# page1.net
KiCad netlist of a schematic drawn in Altium Designer
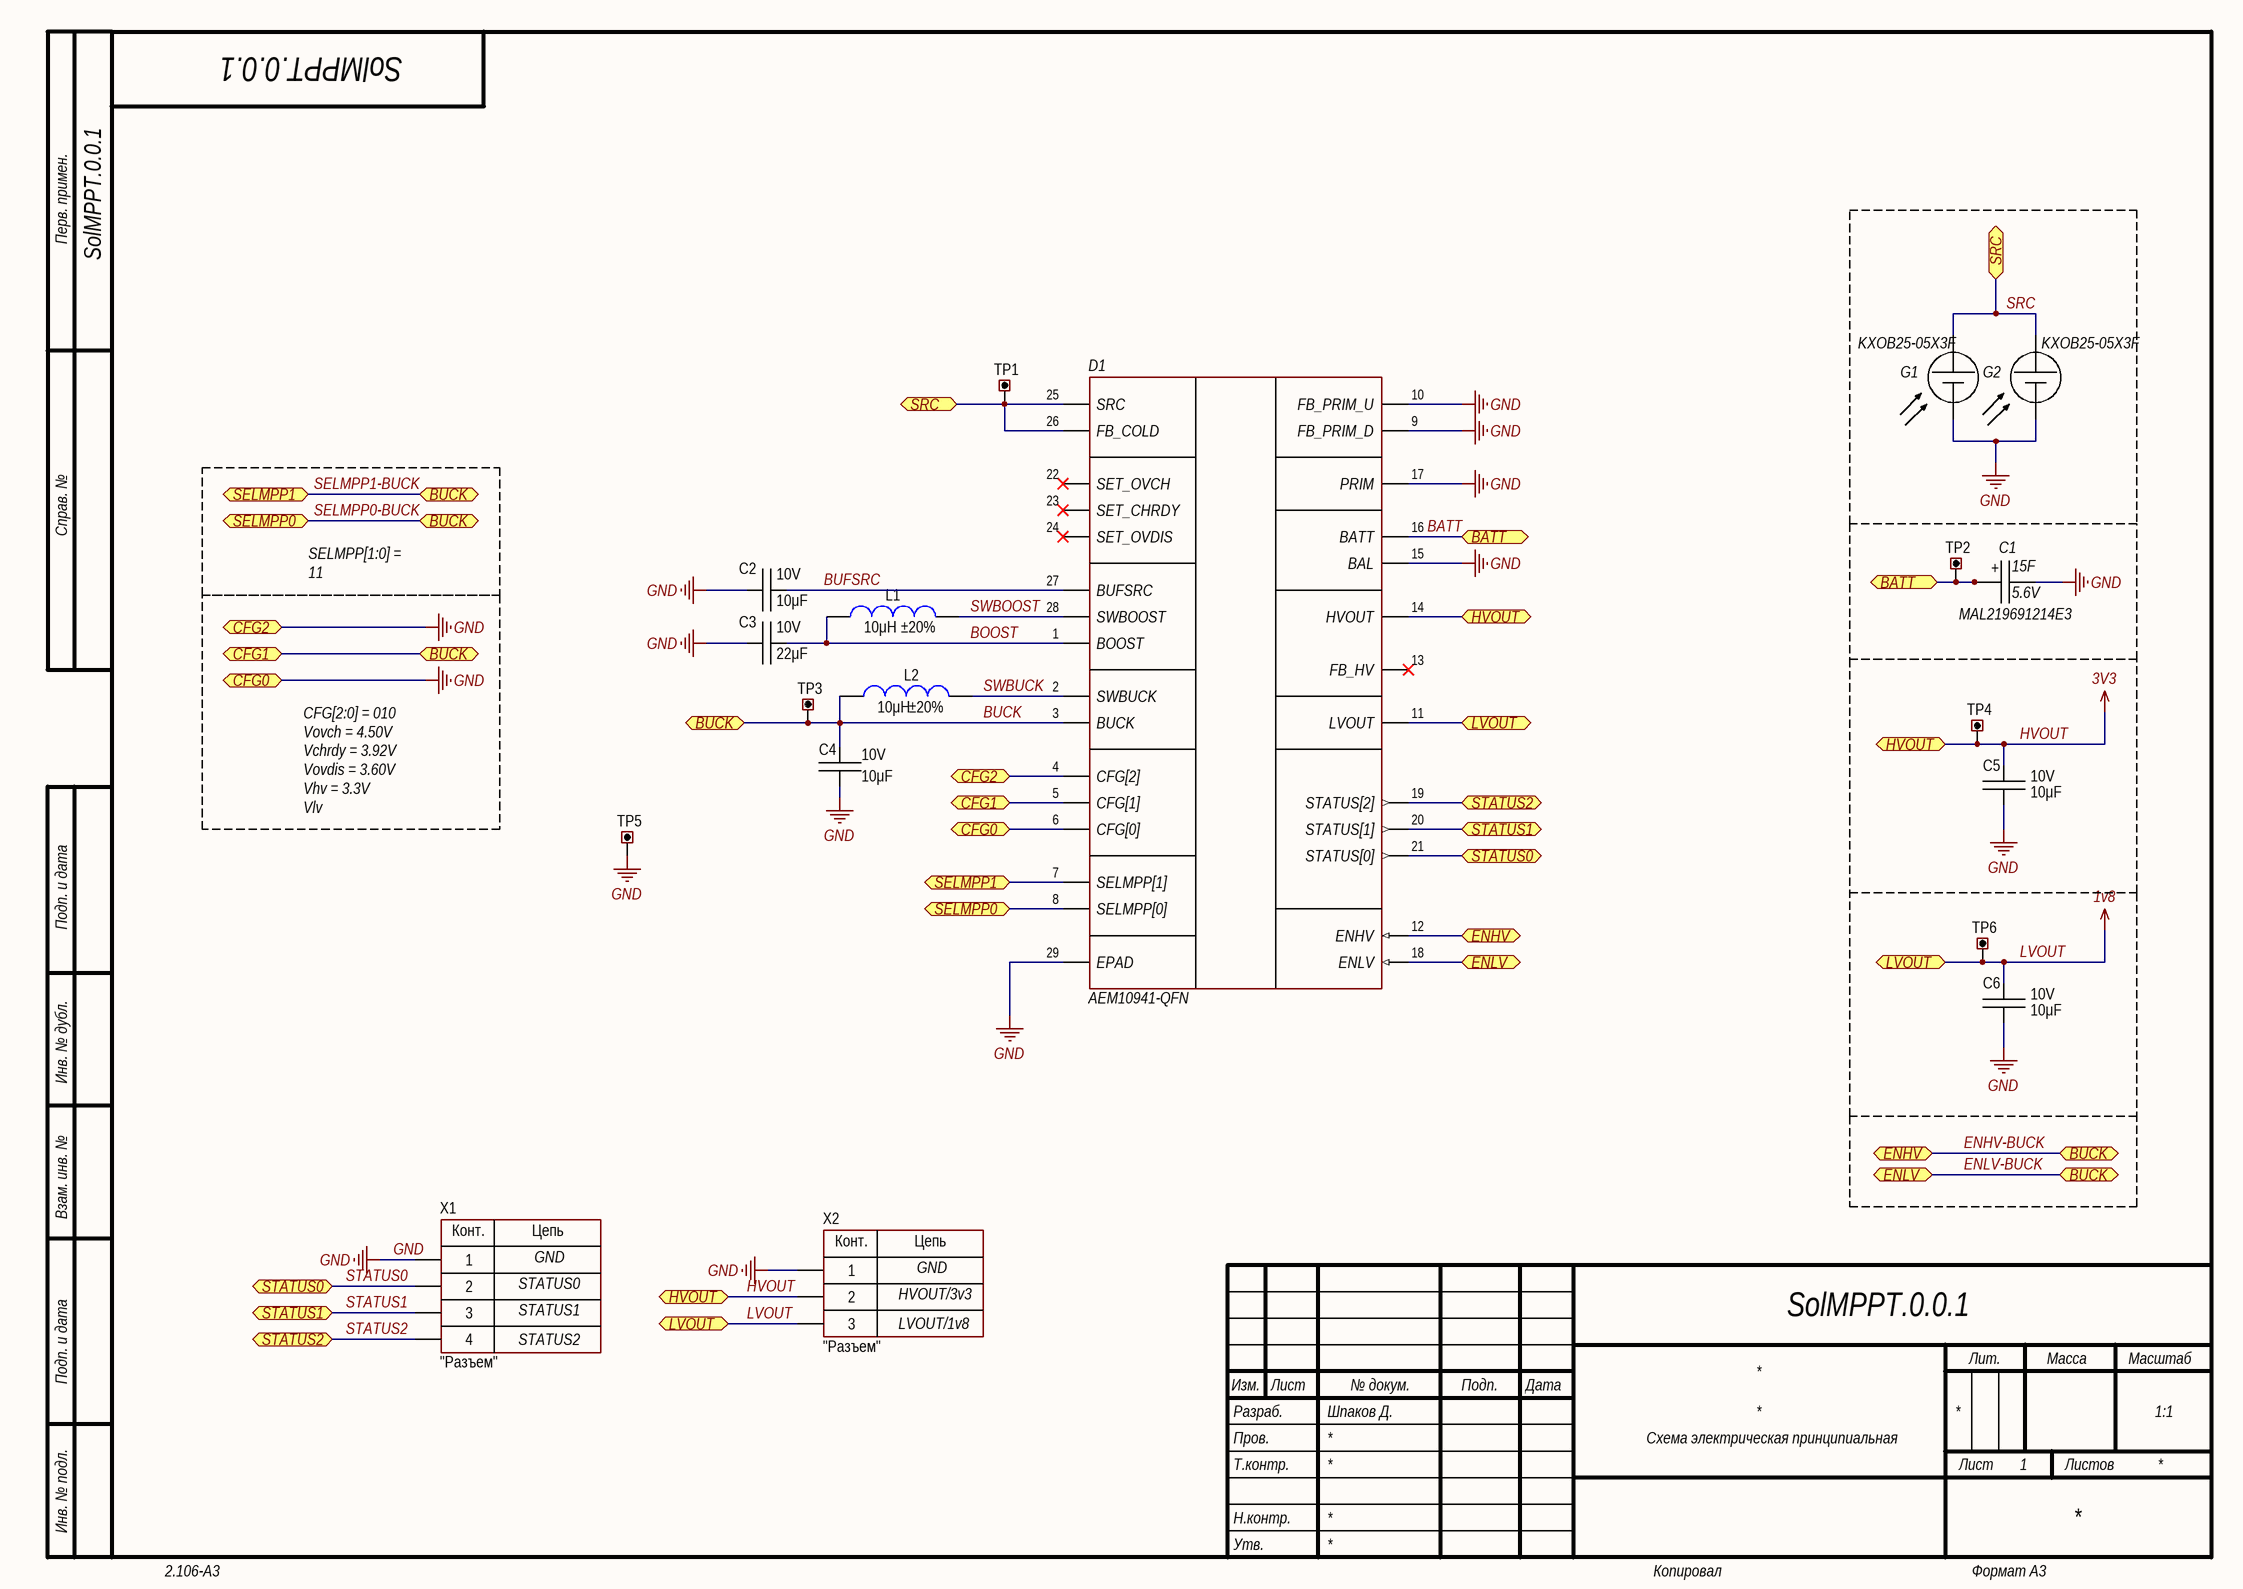
[diagram p0: page1.SchDoc]

(export (version "E")
  (design (tool "Eeschema 10.0.6"))
  (components
    (comp (ref "C1")
      (value "15F")
      (footprint "MAL219691214E3")
      (description "CAP 15F -20% +80% 5.6V T/H")
      (fields
        (field (name "MANUFACTURER") "Vishay Beyschlag/Draloric/BC Components")
        (field (name "PARTNUMBER") "MAL219691214E3")
        (field (name "VOLTAGE") "5.6V")
      )
      (libsource (lib "MAL219691214E3") (part "MAL219691214E3"))
    )
    (comp (ref "C2")
      (value "10μF")
      (footprint "CAP: 0603")
      (fields
        (field (name "MANUFACTURER") "Murata Electronics")
        (field (name "PARTNUMBER") "GRM188R61A106ME69D")
        (field (name "VALUEMANUFACTURERPARTNUMBER") "Ceramic capacitor, 10μF, X5R, ±20%, 10V, 0603, -55...+85°C")
        (field (name "VOLTAGE") "10V")
      )
      (libsource (lib "capacitor") (part "Ceramic_0603"))
    )
    (comp (ref "C3")
      (value "22μF")
      (footprint "CAP: 0603")
      (fields
        (field (name "MANUFACTURER") "Murata Electronics")
        (field (name "PARTNUMBER") "GRM188R61A226ME15D")
        (field (name "VALUEMANUFACTURERPARTNUMBER") "Ceramic capacitor, 22μF, X5R, ±20%, 10V, 0603, -55...+85°C")
        (field (name "VOLTAGE") "10V")
      )
      (libsource (lib "capacitor") (part "Ceramic_0603"))
    )
    (comp (ref "C4")
      (value "10μF")
      (footprint "CAP: 0603")
      (fields
        (field (name "MANUFACTURER") "Murata Electronics")
        (field (name "PARTNUMBER") "GRM188R61A106ME69D")
        (field (name "VALUEMANUFACTURERPARTNUMBER") "Ceramic capacitor, 10μF, X5R, ±20%, 10V, 0603, -55...+85°C")
        (field (name "VOLTAGE") "10V")
      )
      (libsource (lib "capacitor") (part "Ceramic_0603"))
    )
    (comp (ref "C5")
      (value "10μF")
      (footprint "CAP: 0603")
      (fields
        (field (name "MANUFACTURER") "Murata Electronics")
        (field (name "PARTNUMBER") "GRM188R61A106ME69D")
        (field (name "VALUEMANUFACTURERPARTNUMBER") "Ceramic capacitor, 10μF, X5R, ±20%, 10V, 0603, -55...+85°C")
        (field (name "VOLTAGE") "10V")
      )
      (libsource (lib "capacitor") (part "Ceramic_0603"))
    )
    (comp (ref "C6")
      (value "10μF")
      (footprint "CAP: 0603")
      (fields
        (field (name "MANUFACTURER") "Murata Electronics")
        (field (name "PARTNUMBER") "GRM188R61A106ME69D")
        (field (name "VALUEMANUFACTURERPARTNUMBER") "Ceramic capacitor, 10μF, X5R, ±20%, 10V, 0603, -55...+85°C")
        (field (name "VOLTAGE") "10V")
      )
      (libsource (lib "capacitor") (part "Ceramic_0603"))
    )
    (comp (ref "D1")
      (value "AEM10941-QFN")
      (footprint "QFN50P500X500X85_HS-29N")
      (description "Power Management Specialised - PMIC AEM10941 IC - Photovoltaic Energy Harvesting Manager.")
      (fields (field (name "MANUFACTURER") "e-peas"))
      (libsource (lib "AEM10941") (part "AEM10941"))
    )
    (comp (ref "G1")
      (value "KXOB25-05X3F")
      (footprint "KXOB25-05X3F")
      (description "Monocrystalline solar cell.")
      (fields (field (name "MANUFACTURER") "ANYSOLAR Ltd"))
      (libsource (lib "Solar_cell") (part "KXOB25-05X3F"))
    )
    (comp (ref "G2")
      (value "KXOB25-05X3F")
      (footprint "KXOB25-05X3F")
      (description "Monocrystalline solar cell.")
      (fields (field (name "MANUFACTURER") "ANYSOLAR Ltd"))
      (libsource (lib "Solar_cell") (part "KXOB25-05X3F"))
    )
    (comp (ref "L1")
      (value "10μH")
      (footprint "IND: SDR0302")
      (fields
        (field (name "MANUFACTURER") "Bourns")
        (field (name "PARTNUMBER") "SDR0302-100ML")
        (field (name "VALUEMANUFACTURERPARTNUMBER") "Fixed inductor, 10μH, ±20%, SDR0302, 900mA, -40...+125°C")
        (field (name "TOLERANCE") "±20%")
      )
      (libsource (lib "inductor") (part "Inductor_SDR0302"))
    )
    (comp (ref "L2")
      (value "10μH")
      (footprint "IND: 0603")
      (fields
        (field (name "MANUFACTURER") "TDK Corporation")
        (field (name "PARTNUMBER") "MLZ1608M100WT000")
        (field (name "VALUEMANUFACTURERPARTNUMBER") "Fixed inductor, 10μH, ±20%, 0603, 250mA, -55...+125°C")
        (field (name "TOLERANCE") "±20%")
      )
      (libsource (lib "inductor") (part "Inductor_0603"))
    )
    (comp (ref "TP1")
      (value "~")
      (footprint "CON: 5000 (Keystone)")
      (fields
        (field (name "MANUFACTURER") "Keystone")
        (field (name "VALUEMANUFACTURERPARTNUMBER") "Test point, Keystone, 5001")
        (field (name "PARTNUMBER") "5001")
      )
      (libsource (lib "connector") (part "Connector_Test_Point"))
    )
    (comp (ref "TP2")
      (value "~")
      (footprint "CON: 5000 (Keystone)")
      (fields
        (field (name "MANUFACTURER") "Keystone")
        (field (name "VALUEMANUFACTURERPARTNUMBER") "Test point, Keystone, 5001")
        (field (name "PARTNUMBER") "5001")
      )
      (libsource (lib "connector") (part "Connector_Test_Point"))
    )
    (comp (ref "TP3")
      (value "~")
      (footprint "CON: 5000 (Keystone)")
      (fields
        (field (name "MANUFACTURER") "Keystone")
        (field (name "VALUEMANUFACTURERPARTNUMBER") "Test point, Keystone, 5001")
        (field (name "PARTNUMBER") "5001")
      )
      (libsource (lib "connector") (part "Connector_Test_Point"))
    )
    (comp (ref "TP4")
      (value "~")
      (footprint "CON: 5000 (Keystone)")
      (fields
        (field (name "MANUFACTURER") "Keystone")
        (field (name "VALUEMANUFACTURERPARTNUMBER") "Test point, Keystone, 5001")
        (field (name "PARTNUMBER") "5001")
      )
      (libsource (lib "connector") (part "Connector_Test_Point"))
    )
    (comp (ref "TP5")
      (value "~")
      (footprint "CON: 5000 (Keystone)")
      (fields
        (field (name "MANUFACTURER") "Keystone")
        (field (name "VALUEMANUFACTURERPARTNUMBER") "Test point, Keystone, 5001")
        (field (name "PARTNUMBER") "5001")
      )
      (libsource (lib "connector") (part "Connector_Test_Point"))
    )
    (comp (ref "TP6")
      (value "~")
      (footprint "CON: 5000 (Keystone)")
      (fields
        (field (name "MANUFACTURER") "Keystone")
        (field (name "VALUEMANUFACTURERPARTNUMBER") "Test point, Keystone, 5001")
        (field (name "PARTNUMBER") "5001")
      )
      (libsource (lib "connector") (part "Connector_Test_Point"))
    )
    (comp (ref "X1")
      (value "~")
      (footprint "CON: PLS-4")
      (fields
        (field (name "MANUFACTURER") "Connfly")
        (field (name "VALUEMANUFACTURERPARTNUMBER") "Connector, 4pin, 2.54mm, 500VAC, 3A")
        (field (name "PARTNUMBER") "PLS-4")
        (field (name "COMMENTTEXT") "\"Разъем\"")
      )
      (libsource (lib "connector") (part "PLS-4"))
    )
    (comp (ref "X2")
      (value "~")
      (footprint "CON: PLS-3")
      (fields
        (field (name "MANUFACTURER") "Connfly")
        (field (name "VALUEMANUFACTURERPARTNUMBER") "Connector, 3pin, 2.54mm, 500VAC, 3A")
        (field (name "PARTNUMBER") "PLS-3")
        (field (name "COMMENTTEXT") "\"Разъем\"")
      )
      (libsource (lib "connector") (part "PLS-3"))
    )
  )
  (nets
    (net (code "1") (name "/BATT") (class "Default")
      (node (ref "C1") (pin "1") (pintype "power_in"))
      (node (ref "C1") (pin "1a") (pintype "power_in"))
      (node (ref "D1") (pin "16") (pinfunction "BATT_16") (pintype "power_in"))
      (node (ref "TP2") (pin "1") (pinfunction "1_1") (pintype "passive"))
    )
    (net (code "2") (name "/BOOST") (class "Default")
      (node (ref "C3") (pin "1") (pinfunction "1_1") (pintype "passive"))
      (node (ref "D1") (pin "1") (pinfunction "BOOST_1") (pintype "power_in"))
      (node (ref "L1") (pin "2") (pinfunction "2_2") (pintype "passive"))
    )
    (net (code "3") (name "/BUCK") (class "Default")
      (node (ref "C4") (pin "1") (pinfunction "1_1") (pintype "passive"))
      (node (ref "D1") (pin "12") (pinfunction "ENHV_12") (pintype "input"))
      (node (ref "D1") (pin "18") (pinfunction "ENLV_18") (pintype "input"))
      (node (ref "D1") (pin "3") (pinfunction "BUCK_3") (pintype "power_in"))
      (node (ref "D1") (pin "5") (pinfunction "CFG[1]_5") (pintype "power_in"))
      (node (ref "D1") (pin "7") (pinfunction "SELMPP[1]_7") (pintype "power_in"))
      (node (ref "D1") (pin "8") (pinfunction "SELMPP[0]_8") (pintype "power_in"))
      (node (ref "L2") (pin "2") (pinfunction "2_2") (pintype "passive"))
      (node (ref "TP3") (pin "1") (pinfunction "1_1") (pintype "passive"))
    )
    (net (code "4") (name "/BUFSRC") (class "Default")
      (node (ref "C2") (pin "2") (pinfunction "2_2") (pintype "passive"))
      (node (ref "D1") (pin "27") (pinfunction "BUFSRC_27") (pintype "power_in"))
    )
    (net (code "5") (name "/SRC") (class "Default")
      (node (ref "D1") (pin "25") (pinfunction "SRC_25") (pintype "power_in"))
      (node (ref "D1") (pin "26") (pinfunction "FB_COLD_26") (pintype "power_in"))
      (node (ref "G1") (pin "1") (pintype "power_in"))
      (node (ref "G2") (pin "1") (pintype "power_in"))
      (node (ref "TP1") (pin "1") (pinfunction "1_1") (pintype "passive"))
    )
    (net (code "6") (name "/STATUS0") (class "Default")
      (node (ref "D1") (pin "21") (pinfunction "STATUS[0]_21") (pintype "output"))
      (node (ref "X1") (pin "2") (pinfunction "2_2") (pintype "passive"))
    )
    (net (code "7") (name "/STATUS1") (class "Default")
      (node (ref "D1") (pin "20") (pinfunction "STATUS[1]_20") (pintype "output"))
      (node (ref "X1") (pin "3") (pinfunction "3_3") (pintype "power_in"))
    )
    (net (code "8") (name "/STATUS2") (class "Default")
      (node (ref "D1") (pin "19") (pinfunction "STATUS[2]_19") (pintype "output"))
      (node (ref "X1") (pin "4") (pinfunction "4_4") (pintype "power_in"))
    )
    (net (code "9") (name "/SWBOOST") (class "Default")
      (node (ref "D1") (pin "28") (pinfunction "SWBOOST_28") (pintype "power_in"))
      (node (ref "L1") (pin "1") (pinfunction "1_1") (pintype "passive"))
    )
    (net (code "10") (name "/SWBUCK") (class "Default")
      (node (ref "D1") (pin "2") (pinfunction "SWBUCK_2") (pintype "power_in"))
      (node (ref "L2") (pin "1") (pinfunction "1_1") (pintype "passive"))
    )
    (net (code "11") (name "1v8") (class "Default")
      (node (ref "C6") (pin "1") (pinfunction "1_1") (pintype "passive"))
      (node (ref "D1") (pin "11") (pinfunction "LVOUT_11") (pintype "power_in"))
      (node (ref "TP6") (pin "1") (pinfunction "1_1") (pintype "passive"))
      (node (ref "X2") (pin "3") (pinfunction "3_3") (pintype "power_in"))
    )
    (net (code "12") (name "3V3") (class "Default")
      (node (ref "C5") (pin "1") (pinfunction "1_1") (pintype "passive"))
      (node (ref "D1") (pin "14") (pinfunction "HVOUT_14") (pintype "power_in"))
      (node (ref "TP4") (pin "1") (pinfunction "1_1") (pintype "passive"))
      (node (ref "X2") (pin "2") (pinfunction "2_2") (pintype "passive"))
    )
    (net (code "13") (name "GND") (class "Default")
      (node (ref "C1") (pin "2") (pintype "power_in"))
      (node (ref "C2") (pin "1") (pinfunction "1_1") (pintype "passive"))
      (node (ref "C3") (pin "2") (pinfunction "2_2") (pintype "passive"))
      (node (ref "C4") (pin "2") (pinfunction "2_2") (pintype "passive"))
      (node (ref "C5") (pin "2") (pinfunction "2_2") (pintype "passive"))
      (node (ref "C6") (pin "2") (pinfunction "2_2") (pintype "passive"))
      (node (ref "D1") (pin "10") (pinfunction "FB_PRIM_U_10") (pintype "power_in"))
      (node (ref "D1") (pin "15") (pinfunction "BAL_15") (pintype "power_in"))
      (node (ref "D1") (pin "17") (pinfunction "PRIM_17") (pintype "power_in"))
      (node (ref "D1") (pin "29") (pinfunction "EPAD_29") (pintype "power_in"))
      (node (ref "D1") (pin "4") (pinfunction "CFG[2]_4") (pintype "power_in"))
      (node (ref "D1") (pin "6") (pinfunction "CFG[0]_6") (pintype "power_in"))
      (node (ref "D1") (pin "9") (pinfunction "FB_PRIM_D_9") (pintype "power_in"))
      (node (ref "G1") (pin "2") (pintype "power_in"))
      (node (ref "G2") (pin "2") (pintype "power_in"))
      (node (ref "TP5") (pin "1") (pinfunction "1_1") (pintype "passive"))
      (node (ref "X1") (pin "1") (pinfunction "1_1") (pintype "passive"))
      (node (ref "X2") (pin "1") (pinfunction "1_1") (pintype "passive"))
    )
    (net (code "14") (name "unconnected-(D1-FB_HV-Pad13)") (class "Default")
      (node (ref "D1") (pin "13") (pinfunction "FB_HV_13") (pintype "power_in+no_connect"))
    )
    (net (code "15") (name "unconnected-(D1-SET_CHRDY-Pad23)") (class "Default")
      (node (ref "D1") (pin "23") (pinfunction "SET_CHRDY_23") (pintype "power_in+no_connect"))
    )
    (net (code "16") (name "unconnected-(D1-SET_OVCH-Pad22)") (class "Default")
      (node (ref "D1") (pin "22") (pinfunction "SET_OVCH_22") (pintype "power_in+no_connect"))
    )
    (net (code "17") (name "unconnected-(D1-SET_OVDIS-Pad24)") (class "Default")
      (node (ref "D1") (pin "24") (pinfunction "SET_OVDIS_24") (pintype "power_in+no_connect"))
    )
  )
)
